# CAN_Bus.net
KiCad netlist of a schematic drawn in Altium Designer
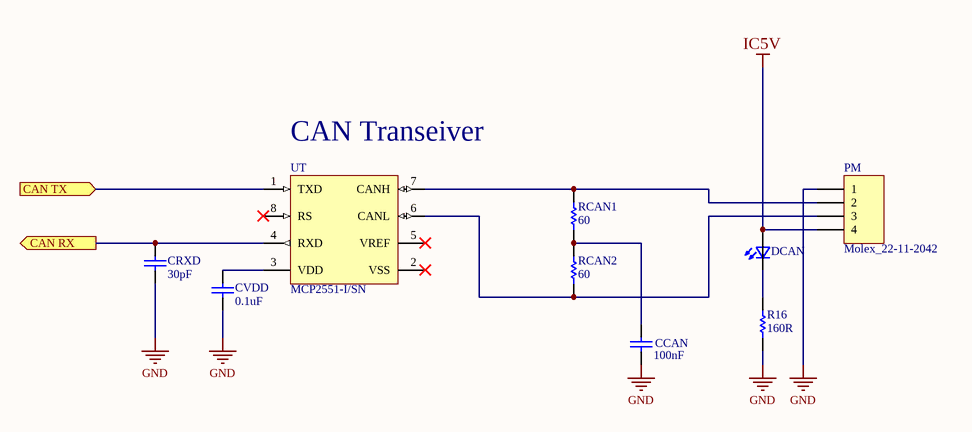
[diagram p0: CAN_Bus.SchDoc]

(export (version "E")
  (design (tool "Eeschema 10.0.6"))
  (components
    (comp (ref "CCAN")
      (value "100nF")
      (description "Capacitor")
      (libsource (lib "Simulation Generic Components") (part "Capacitor"))
    )
    (comp (ref "CRXD")
      (value "30pF")
      (description "Capacitor")
      (libsource (lib "Simulation Generic Components") (part "Capacitor"))
    )
    (comp (ref "CVDD")
      (value "0.1uF")
      (description "Capacitor")
      (libsource (lib "Simulation Generic Components") (part "Capacitor"))
    )
    (comp (ref "DCAN")
      (value "LTST-S270KRKT")
      (footprint "0603")
      (description "http://octopart.com/ltst-c190tbkt-lite-on-550003\r\n\r\nBlue LED")
      (fields (field (name "MF") "{'manufacturer': u'Lite-On Inc.'}"))
      (libsource (lib "LTST-S270KRKT") (part "LTST-S270KRKT"))
    )
    (comp (ref "PM")
      (value "Molex_22-11-2042")
      (footprint "MOLEX-22-11-2042")
      (description "CONN HEADER 4POS .100 VERT GOLD")
      (fields (field (name "MPN") "0022112042"))
      (libsource (lib "esd_library") (part "Molex_22-11-2042"))
    )
    (comp (ref "R16")
      (value "160R")
      (description "Resistor")
      (libsource (lib "Simulation Generic Components") (part "Resistor"))
    )
    (comp (ref "RCAN1")
      (value "60")
      (description "Resistor")
      (libsource (lib "Simulation Generic Components") (part "Resistor"))
    )
    (comp (ref "RCAN2")
      (value "60")
      (description "Resistor")
      (libsource (lib "Simulation Generic Components") (part "Resistor"))
    )
    (comp (ref "UT")
      (value "MCP2551-I/SN")
      (footprint "MCHP-SN8_V")
      (fields (field (name "MANUFACTURER") "Microchip"))
      (libsource (lib "Altium Content Vault") (part "MCHP-MCP2551-SN8"))
    )
  )
  (nets
    (net (code "1") (name "/CAN RX") (class "Default")
      (node (ref "CRXD") (pin "2") (pinfunction "2_2") (pintype "passive"))
      (node (ref "UT") (pin "4") (pinfunction "RXD_4") (pintype "output"))
    )
    (net (code "2") (name "/CAN TX") (class "Default")
      (node (ref "UT") (pin "1") (pinfunction "TXD_1") (pintype "input"))
    )
    (net (code "3") (name "GND") (class "Default")
      (node (ref "CCAN") (pin "1") (pinfunction "1_1") (pintype "passive"))
      (node (ref "CRXD") (pin "1") (pinfunction "1_1") (pintype "passive"))
      (node (ref "CVDD") (pin "1") (pinfunction "1_1") (pintype "passive"))
      (node (ref "PM") (pin "1") (pinfunction "1_1") (pintype "passive"))
      (node (ref "R16") (pin "1") (pinfunction "1_1") (pintype "passive"))
    )
    (net (code "4") (name "IC5V") (class "Default")
      (node (ref "DCAN") (pin "2") (pinfunction "A2_2") (pintype "passive"))
      (node (ref "PM") (pin "4") (pinfunction "4_4") (pintype "passive"))
    )
    (net (code "5") (name "Net-(CCAN-Pad2)") (class "Default")
      (node (ref "CCAN") (pin "2") (pinfunction "2_2") (pintype "passive"))
      (node (ref "RCAN1") (pin "1") (pinfunction "1_1") (pintype "passive"))
      (node (ref "RCAN2") (pin "2") (pinfunction "2_2") (pintype "passive"))
    )
    (net (code "6") (name "Net-(DCAN-K2)") (class "Default")
      (node (ref "DCAN") (pin "1") (pinfunction "K2_1") (pintype "passive"))
      (node (ref "R16") (pin "2") (pinfunction "2_2") (pintype "passive"))
    )
    (net (code "7") (name "Net-(UT-CANH)") (class "Default")
      (node (ref "PM") (pin "2") (pinfunction "2_2") (pintype "passive"))
      (node (ref "RCAN1") (pin "2") (pinfunction "2_2") (pintype "passive"))
      (node (ref "UT") (pin "7") (pinfunction "CANH_7") (pintype "bidirectional"))
    )
    (net (code "8") (name "Net-(UT-CANL)") (class "Default")
      (node (ref "PM") (pin "3") (pinfunction "3_3") (pintype "passive"))
      (node (ref "RCAN2") (pin "1") (pinfunction "1_1") (pintype "passive"))
      (node (ref "UT") (pin "6") (pinfunction "CANL_6") (pintype "bidirectional"))
    )
    (net (code "9") (name "Net-(UT-VDD)") (class "Default")
      (node (ref "CVDD") (pin "2") (pinfunction "2_2") (pintype "passive"))
      (node (ref "UT") (pin "3") (pinfunction "VDD_3") (pintype "power_in"))
    )
    (net (code "10") (name "unconnected-(UT-RS-Pad8)") (class "Default")
      (node (ref "UT") (pin "8") (pinfunction "RS_8") (pintype "input+no_connect"))
    )
    (net (code "11") (name "unconnected-(UT-VREF-Pad5)") (class "Default")
      (node (ref "UT") (pin "5") (pinfunction "VREF_5") (pintype "power_in+no_connect"))
    )
    (net (code "12") (name "unconnected-(UT-VSS-Pad2)") (class "Default")
      (node (ref "UT") (pin "2") (pinfunction "VSS_2") (pintype "power_in+no_connect"))
    )
  )
)
